# iSystem-arduino_connector.net
KiCad netlist of a schematic drawn in Altium Designer
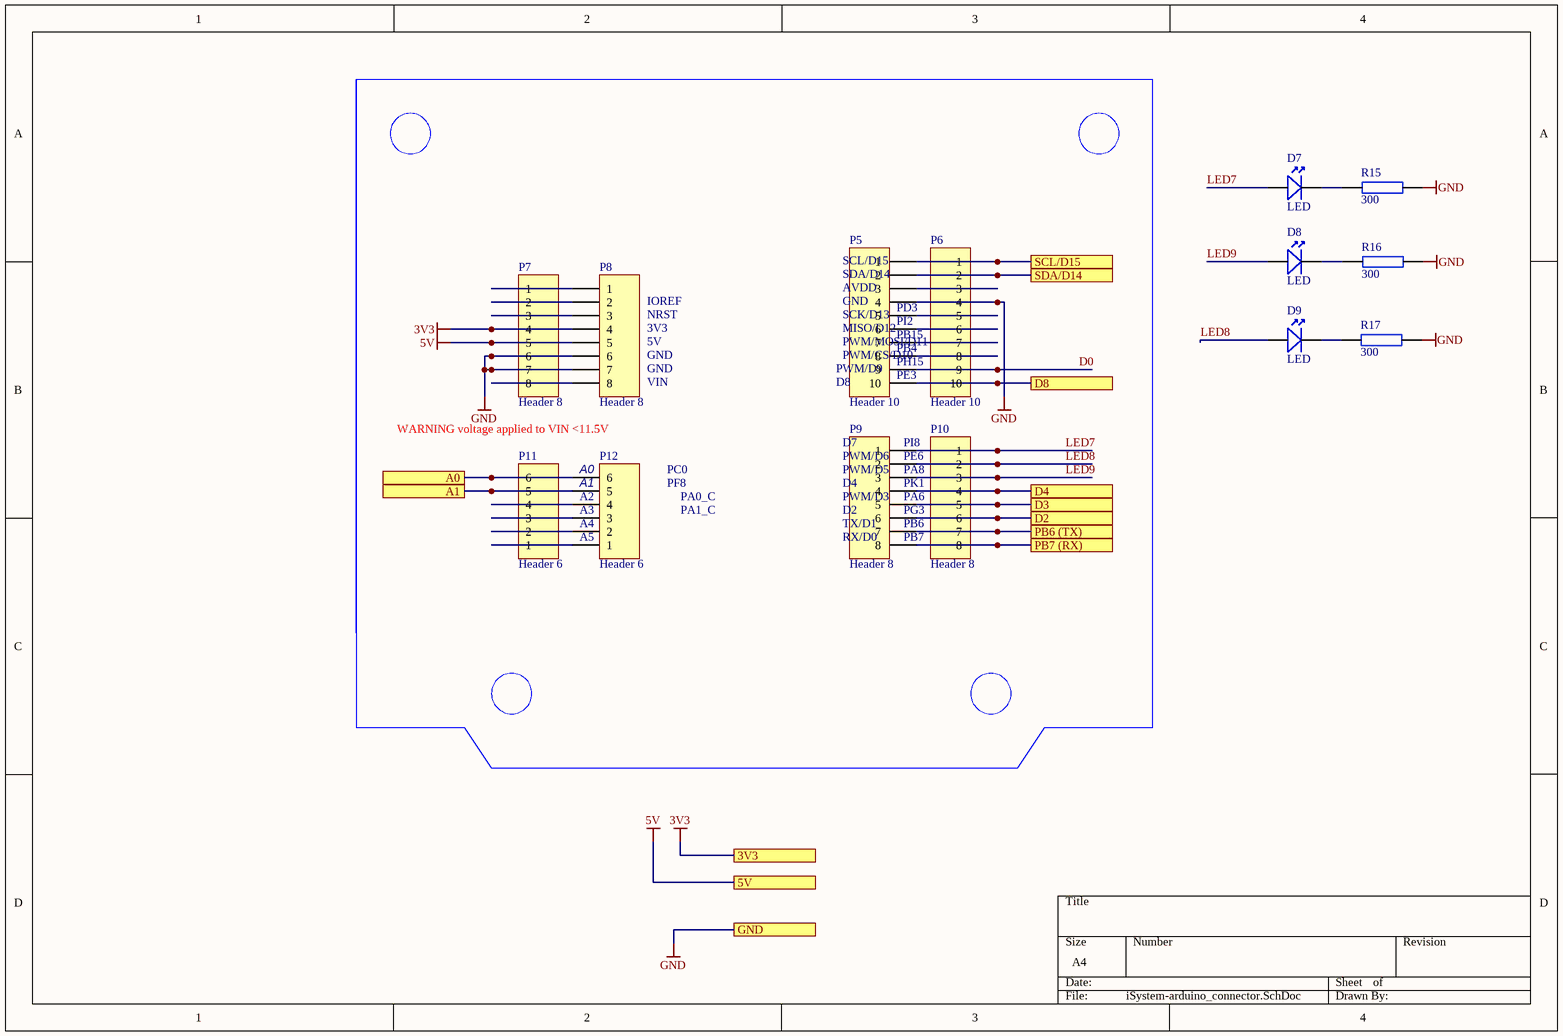
[diagram p0: iSystem-arduino_connector.SchDoc]

(export (version "E")
  (design (tool "Eeschema 10.0.6"))
  (components
    (comp (ref "D7") (value "LED") (footprint "0805 LED RED") (libsource (lib "Diodes") (part "LED")))
    (comp (ref "D8") (value "LED") (footprint "0805 LED RED") (libsource (lib "Diodes") (part "LED")))
    (comp (ref "D9") (value "LED") (footprint "0805 LED RED") (libsource (lib "Diodes") (part "LED")))
    (comp (ref "P5")
      (value "Header 10")
      (footprint "HDR1X10")
      (description "Header, 10-Pin")
      (fields (field (name "PUBLISHER") "Altium Limited"))
      (libsource (lib "Miscellaneous Connectors") (part "Header 10"))
    )
    (comp (ref "P6")
      (value "Header 10")
      (footprint "HDR1X10")
      (description "Header, 10-Pin")
      (fields (field (name "PUBLISHER") "Altium Limited"))
      (libsource (lib "Miscellaneous Connectors") (part "Header 10"))
    )
    (comp (ref "P7")
      (value "Header 8")
      (footprint "HDR1X8")
      (description "Header, 8-Pin")
      (fields (field (name "PUBLISHER") "Altium Limited"))
      (libsource (lib "Miscellaneous Connectors") (part "Header 8"))
    )
    (comp (ref "P8")
      (value "Header 8")
      (footprint "HDR1X8")
      (description "Header, 8-Pin")
      (fields (field (name "PUBLISHER") "Altium Limited"))
      (libsource (lib "Miscellaneous Connectors") (part "Header 8"))
    )
    (comp (ref "P9")
      (value "Header 8")
      (footprint "HDR1X8")
      (description "Header, 8-Pin")
      (fields (field (name "PUBLISHER") "Altium Limited"))
      (libsource (lib "") (part "Header 8_1"))
    )
    (comp (ref "P10")
      (value "Header 8")
      (footprint "HDR1X8")
      (description "Header, 8-Pin")
      (fields (field (name "PUBLISHER") "Altium Limited"))
      (libsource (lib "") (part "Header 8_1"))
    )
    (comp (ref "P11")
      (value "Header 6")
      (footprint "HDR1X6")
      (description "Header, 6-Pin")
      (fields (field (name "PUBLISHER") "Altium Limited"))
      (libsource (lib "Miscellaneous Connectors") (part "Header 6"))
    )
    (comp (ref "P12")
      (value "Header 6")
      (footprint "HDR1X6")
      (description "Header, 6-Pin")
      (fields (field (name "PUBLISHER") "Altium Limited"))
      (libsource (lib "Miscellaneous Connectors") (part "Header 6"))
    )
    (comp (ref "R15")
      (value "300")
      (footprint "0603")
      (description "Resistor")
      (libsource (lib "General") (part "Resistor"))
    )
    (comp (ref "R16")
      (value "300")
      (footprint "0603")
      (description "Resistor")
      (libsource (lib "General") (part "Resistor"))
    )
    (comp (ref "R17")
      (value "300")
      (footprint "0603")
      (description "Resistor")
      (libsource (lib "General") (part "Resistor"))
    )
  )
  (nets
    (net (code "1") (name "/A0") (class "Default")
      (node (ref "P11") (pin "6") (pinfunction "6_6") (pintype "passive"))
      (node (ref "P12") (pin "6") (pinfunction "6_6") (pintype "passive"))
    )
    (net (code "2") (name "/A1") (class "Default")
      (node (ref "P11") (pin "5") (pinfunction "5_5") (pintype "passive"))
      (node (ref "P12") (pin "5") (pinfunction "5_5") (pintype "passive"))
    )
    (net (code "3") (name "/D0") (class "Default")
      (node (ref "P5") (pin "9") (pinfunction "9_9") (pintype "passive"))
      (node (ref "P6") (pin "9") (pinfunction "9_9") (pintype "passive"))
    )
    (net (code "4") (name "/D2") (class "Default")
      (node (ref "P10") (pin "6") (pinfunction "6_6") (pintype "passive"))
      (node (ref "P9") (pin "6") (pinfunction "6_6") (pintype "passive"))
    )
    (net (code "5") (name "/D3") (class "Default")
      (node (ref "P10") (pin "5") (pinfunction "5_5") (pintype "passive"))
      (node (ref "P9") (pin "5") (pinfunction "5_5") (pintype "passive"))
    )
    (net (code "6") (name "/D4") (class "Default")
      (node (ref "P10") (pin "4") (pinfunction "4_4") (pintype "passive"))
      (node (ref "P9") (pin "4") (pinfunction "4_4") (pintype "passive"))
    )
    (net (code "7") (name "/D8") (class "Default")
      (node (ref "P5") (pin "10") (pinfunction "10_10") (pintype "passive"))
      (node (ref "P6") (pin "10") (pinfunction "10_10") (pintype "passive"))
    )
    (net (code "8") (name "/LED7") (class "Default")
      (node (ref "D7") (pin "1") (pinfunction "A_1") (pintype "passive"))
      (node (ref "P10") (pin "1") (pinfunction "1_1") (pintype "passive"))
      (node (ref "P9") (pin "1") (pinfunction "1_1") (pintype "passive"))
    )
    (net (code "9") (name "/LED8") (class "Default")
      (node (ref "D9") (pin "1") (pinfunction "A_1") (pintype "passive"))
      (node (ref "P10") (pin "2") (pinfunction "2_2") (pintype "passive"))
      (node (ref "P9") (pin "2") (pinfunction "2_2") (pintype "passive"))
    )
    (net (code "10") (name "/LED9") (class "Default")
      (node (ref "D8") (pin "1") (pinfunction "A_1") (pintype "passive"))
      (node (ref "P10") (pin "3") (pinfunction "3_3") (pintype "passive"))
      (node (ref "P9") (pin "3") (pinfunction "3_3") (pintype "passive"))
    )
    (net (code "11") (name "/PB6 (TX)") (class "Default")
      (node (ref "P10") (pin "7") (pinfunction "7_7") (pintype "passive"))
      (node (ref "P9") (pin "7") (pinfunction "7_7") (pintype "passive"))
    )
    (net (code "12") (name "/PB7 (RX)") (class "Default")
      (node (ref "P10") (pin "8") (pinfunction "8_8") (pintype "passive"))
      (node (ref "P9") (pin "8") (pinfunction "8_8") (pintype "passive"))
    )
    (net (code "13") (name "/SCL{slash}D15") (class "Default")
      (node (ref "P5") (pin "1") (pinfunction "1_1") (pintype "passive"))
      (node (ref "P6") (pin "1") (pinfunction "1_1") (pintype "passive"))
    )
    (net (code "14") (name "/SDA{slash}D14") (class "Default")
      (node (ref "P5") (pin "2") (pinfunction "2_2") (pintype "passive"))
      (node (ref "P6") (pin "2") (pinfunction "2_2") (pintype "passive"))
    )
    (net (code "15") (name "3V3") (class "Default")
      (node (ref "P7") (pin "4") (pinfunction "4_4") (pintype "passive"))
      (node (ref "P8") (pin "4") (pinfunction "4_4") (pintype "passive"))
    )
    (net (code "16") (name "5V") (class "Default")
      (node (ref "P7") (pin "5") (pinfunction "5_5") (pintype "passive"))
      (node (ref "P8") (pin "5") (pinfunction "5_5") (pintype "passive"))
    )
    (net (code "17") (name "GND") (class "Default")
      (node (ref "P5") (pin "4") (pinfunction "4_4") (pintype "passive"))
      (node (ref "P6") (pin "4") (pinfunction "4_4") (pintype "passive"))
      (node (ref "P7") (pin "6") (pinfunction "6_6") (pintype "passive"))
      (node (ref "P7") (pin "7") (pinfunction "7_7") (pintype "passive"))
      (node (ref "P8") (pin "6") (pinfunction "6_6") (pintype "passive"))
      (node (ref "P8") (pin "7") (pinfunction "7_7") (pintype "passive"))
      (node (ref "R15") (pin "1") (pintype "passive"))
      (node (ref "R16") (pin "1") (pintype "passive"))
      (node (ref "R17") (pin "1") (pintype "passive"))
    )
    (net (code "18") (name "Net-(D7-K)") (class "Default")
      (node (ref "D7") (pin "2") (pinfunction "K_2") (pintype "passive"))
      (node (ref "R15") (pin "2") (pintype "passive"))
    )
    (net (code "19") (name "Net-(D8-K)") (class "Default")
      (node (ref "D8") (pin "2") (pinfunction "K_2") (pintype "passive"))
      (node (ref "R16") (pin "2") (pintype "passive"))
    )
    (net (code "20") (name "Net-(D9-K)") (class "Default")
      (node (ref "D9") (pin "2") (pinfunction "K_2") (pintype "passive"))
      (node (ref "R17") (pin "2") (pintype "passive"))
    )
    (net (code "21") (name "Net-(P5-Pad3)") (class "Default")
      (node (ref "P5") (pin "3") (pinfunction "3_3") (pintype "passive"))
      (node (ref "P6") (pin "3") (pinfunction "3_3") (pintype "passive"))
    )
    (net (code "22") (name "Net-(P5-Pad5)") (class "Default")
      (node (ref "P5") (pin "5") (pinfunction "5_5") (pintype "passive"))
      (node (ref "P6") (pin "5") (pinfunction "5_5") (pintype "passive"))
    )
    (net (code "23") (name "Net-(P5-Pad6)") (class "Default")
      (node (ref "P5") (pin "6") (pinfunction "6_6") (pintype "passive"))
      (node (ref "P6") (pin "6") (pinfunction "6_6") (pintype "passive"))
    )
    (net (code "24") (name "Net-(P5-Pad7)") (class "Default")
      (node (ref "P5") (pin "7") (pinfunction "7_7") (pintype "passive"))
      (node (ref "P6") (pin "7") (pinfunction "7_7") (pintype "passive"))
    )
    (net (code "25") (name "Net-(P5-Pad8)") (class "Default")
      (node (ref "P5") (pin "8") (pinfunction "8_8") (pintype "passive"))
      (node (ref "P6") (pin "8") (pinfunction "8_8") (pintype "passive"))
    )
    (net (code "26") (name "Net-(P7-Pad1)") (class "Default")
      (node (ref "P7") (pin "1") (pinfunction "1_1") (pintype "passive"))
      (node (ref "P8") (pin "1") (pinfunction "1_1") (pintype "passive"))
    )
    (net (code "27") (name "Net-(P7-Pad2)") (class "Default")
      (node (ref "P7") (pin "2") (pinfunction "2_2") (pintype "passive"))
      (node (ref "P8") (pin "2") (pinfunction "2_2") (pintype "passive"))
    )
    (net (code "28") (name "Net-(P7-Pad3)") (class "Default")
      (node (ref "P7") (pin "3") (pinfunction "3_3") (pintype "passive"))
      (node (ref "P8") (pin "3") (pinfunction "3_3") (pintype "passive"))
    )
    (net (code "29") (name "Net-(P7-Pad8)") (class "Default")
      (node (ref "P7") (pin "8") (pinfunction "8_8") (pintype "passive"))
      (node (ref "P8") (pin "8") (pinfunction "8_8") (pintype "passive"))
    )
    (net (code "30") (name "Net-(P11-Pad1)") (class "Default")
      (node (ref "P11") (pin "1") (pinfunction "1_1") (pintype "passive"))
      (node (ref "P12") (pin "1") (pinfunction "1_1") (pintype "passive"))
    )
    (net (code "31") (name "Net-(P11-Pad2)") (class "Default")
      (node (ref "P11") (pin "2") (pinfunction "2_2") (pintype "passive"))
      (node (ref "P12") (pin "2") (pinfunction "2_2") (pintype "passive"))
    )
    (net (code "32") (name "Net-(P11-Pad3)") (class "Default")
      (node (ref "P11") (pin "3") (pinfunction "3_3") (pintype "passive"))
      (node (ref "P12") (pin "3") (pinfunction "3_3") (pintype "passive"))
    )
    (net (code "33") (name "Net-(P11-Pad4)") (class "Default")
      (node (ref "P11") (pin "4") (pinfunction "4_4") (pintype "passive"))
      (node (ref "P12") (pin "4") (pinfunction "4_4") (pintype "passive"))
    )
  )
)
